# RFM69OP.net
KiCad netlist of a schematic drawn in EAGLE
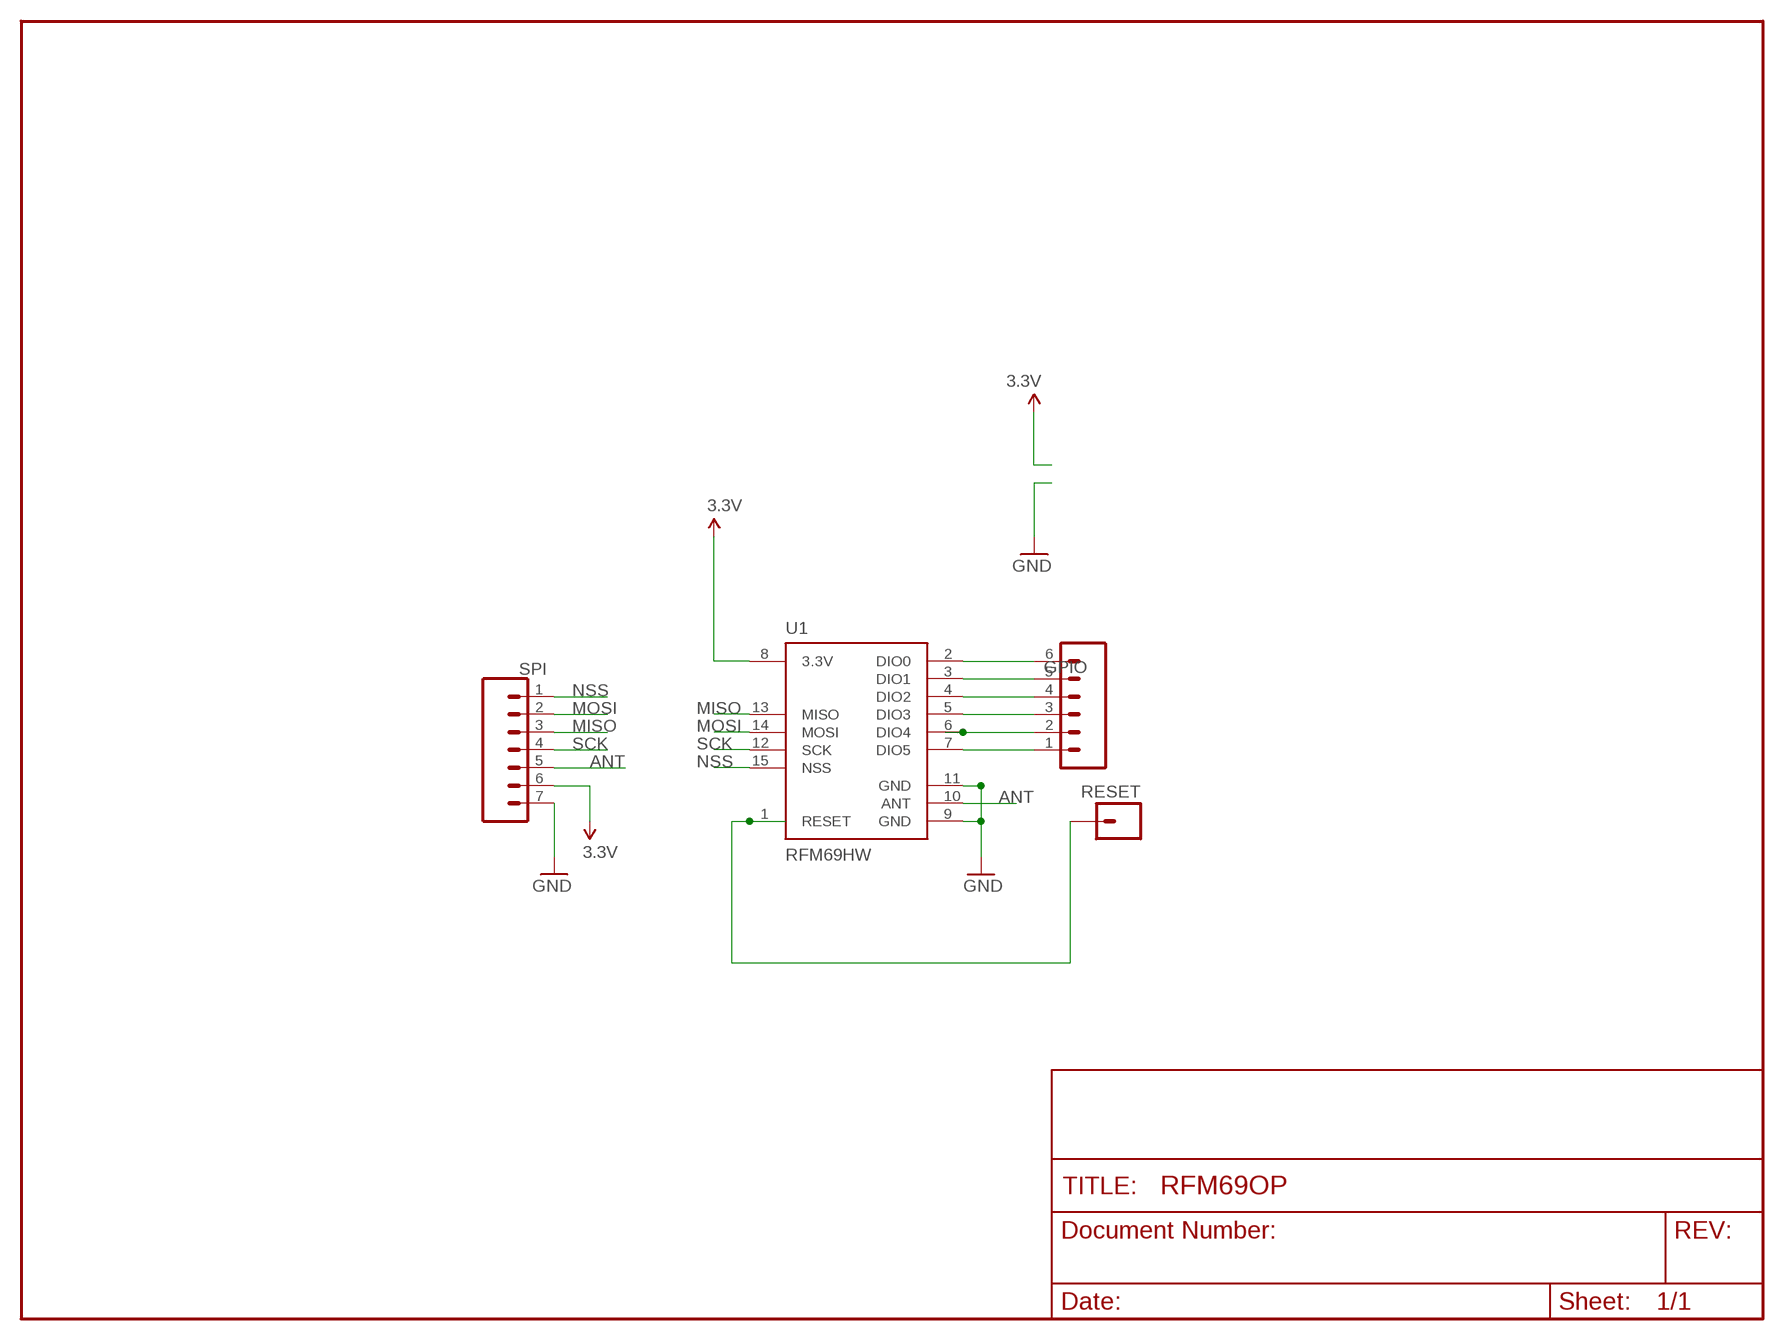
[diagram p0: schematic, sheet 1]

(export (version "E")
  (design (tool "Eeschema 10.0.6"))
  (components
    (comp (ref "JP2")
      (value "RESET")
      (footprint "eagle-import:1X01")
      (libsource (lib "eagle-import") (part "M01PTH"))
    )
    (comp (ref "JP3")
      (value "GPIO")
      (footprint "eagle-import:1X06_LOCK")
      (libsource (lib "eagle-import") (part "M06LOCK"))
    )
    (comp (ref "JP4")
      (value "SPI")
      (footprint "eagle-import:1X07_LOCK")
      (libsource (lib "eagle-import") (part "M07LOCK"))
    )
    (comp (ref "U1")
      (value "RFM69HW")
      (footprint "eagle-import:RFM69W-XXXS2")
      (libsource (lib "eagle-import") (part "RFM69HW"))
    )
  )
  (nets
    (net (code "1") (name "/ANT") (class "Default")
      (node (ref "JP4") (pin "5") (pinfunction "5_5") (pintype "passive"))
      (node (ref "U1") (pin "10") (pinfunction "ANT_10") (pintype "passive"))
    )
    (net (code "2") (name "/MISO") (class "Default")
      (node (ref "JP4") (pin "3") (pinfunction "3_3") (pintype "passive"))
      (node (ref "U1") (pin "13") (pinfunction "MISO_13") (pintype "bidirectional"))
    )
    (net (code "3") (name "/MOSI") (class "Default")
      (node (ref "JP4") (pin "2") (pinfunction "2_2") (pintype "passive"))
      (node (ref "U1") (pin "14") (pinfunction "MOSI_14") (pintype "input"))
    )
    (net (code "4") (name "/NSS") (class "Default")
      (node (ref "JP4") (pin "1") (pinfunction "1_1") (pintype "passive"))
      (node (ref "U1") (pin "15") (pinfunction "NSS_15") (pintype "input"))
    )
    (net (code "5") (name "/SCK") (class "Default")
      (node (ref "JP4") (pin "4") (pinfunction "4_4") (pintype "passive"))
      (node (ref "U1") (pin "12") (pinfunction "SCK_12") (pintype "input"))
    )
    (net (code "6") (name "3.3V") (class "Default")
      (node (ref "JP4") (pin "6") (pinfunction "6_6") (pintype "passive"))
      (node (ref "U1") (pin "8") (pinfunction "3.3V_8") (pintype "power_in"))
    )
    (net (code "7") (name "GND") (class "Default")
      (node (ref "JP4") (pin "7") (pinfunction "7_7") (pintype "passive"))
      (node (ref "U1") (pin "11") (pinfunction "GND_11") (pintype "power_in"))
      (node (ref "U1") (pin "9") (pinfunction "GND_9") (pintype "power_in"))
    )
    (net (code "8") (name "Net-(U1-DIO0)") (class "Default")
      (node (ref "JP3") (pin "6") (pinfunction "6_6") (pintype "passive"))
      (node (ref "U1") (pin "2") (pinfunction "DIO0_2") (pintype "bidirectional"))
    )
    (net (code "9") (name "Net-(U1-DIO1)") (class "Default")
      (node (ref "JP3") (pin "5") (pinfunction "5_5") (pintype "passive"))
      (node (ref "U1") (pin "3") (pinfunction "DIO1_3") (pintype "bidirectional"))
    )
    (net (code "10") (name "Net-(U1-DIO2)") (class "Default")
      (node (ref "JP3") (pin "4") (pinfunction "4_4") (pintype "passive"))
      (node (ref "U1") (pin "4") (pinfunction "DIO2_4") (pintype "bidirectional"))
    )
    (net (code "11") (name "Net-(U1-DIO3)") (class "Default")
      (node (ref "JP3") (pin "3") (pinfunction "3_3") (pintype "passive"))
      (node (ref "U1") (pin "5") (pinfunction "DIO3_5") (pintype "bidirectional"))
    )
    (net (code "12") (name "Net-(U1-DIO4)") (class "Default")
      (node (ref "JP3") (pin "2") (pinfunction "2_2") (pintype "passive"))
      (node (ref "U1") (pin "6") (pinfunction "DIO4_6") (pintype "bidirectional"))
    )
    (net (code "13") (name "Net-(U1-DIO5)") (class "Default")
      (node (ref "JP3") (pin "1") (pinfunction "1_1") (pintype "passive"))
      (node (ref "U1") (pin "7") (pinfunction "DIO5_7") (pintype "bidirectional"))
    )
    (net (code "14") (name "Net-(U1-RESET)") (class "Default")
      (node (ref "JP2") (pin "1") (pinfunction "1_1") (pintype "passive"))
      (node (ref "U1") (pin "1") (pinfunction "RESET_1") (pintype "input"))
    )
  )
)
